# SINTETIZADOR_Y_DDS_SLAVE.net
KiCad netlist of a schematic drawn in Altium Designer
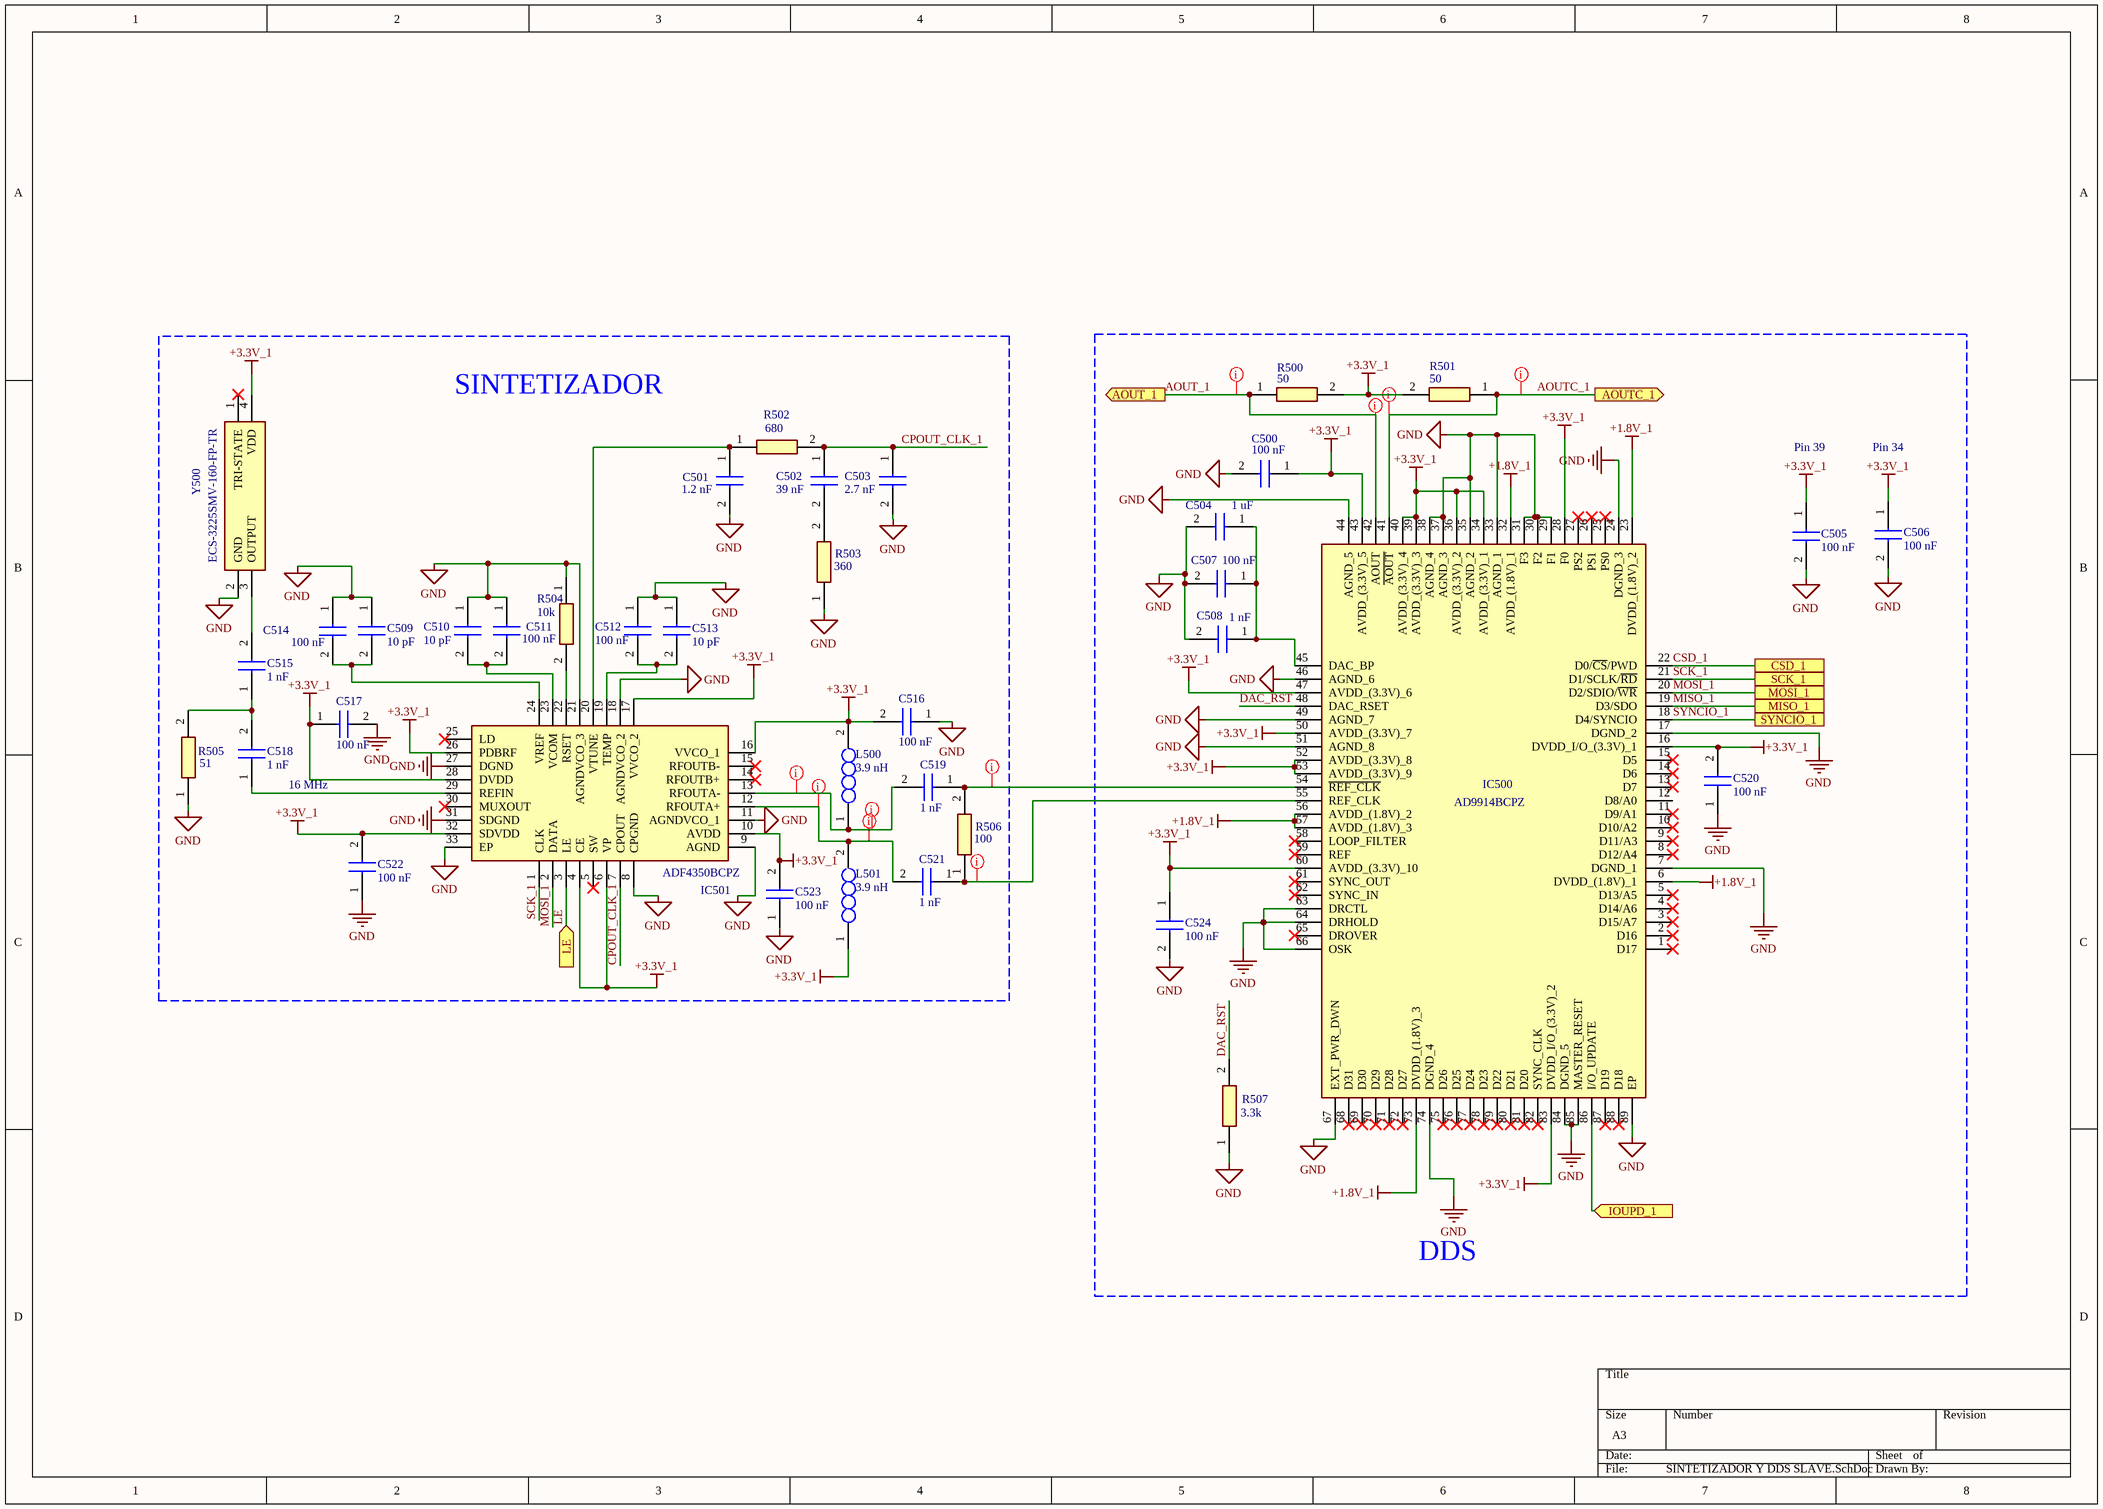
[diagram p0: SINTETIZADOR Y DDS SLAVE.SchDoc]

(export (version "E")
  (design (tool "Eeschema 10.0.6"))
  (components
    (comp (ref "C500")
      (value "100 nF")
      (footprint "SamacSys:C0603")
      (description "Capacitor")
      (fields (field (name "MANUFACTURER_PART_NUMBER") "C0603H470J5GACTU"))
      (libsource (lib "LIBRERIA_GEN_V2.0") (part "C0603H470J5GACTU"))
    )
    (comp (ref "C501")
      (value "1.2 nF")
      (footprint "SamacSys:C0603")
      (description "Capacitor")
      (fields (field (name "MANUFACTURER_PART_NUMBER") "C0603H470J5GACTU"))
      (libsource (lib "LIBRERIA_GEN_V2.0") (part "C0603H470J5GACTU"))
    )
    (comp (ref "C502")
      (value "39 nF")
      (footprint "SamacSys:C0603")
      (description "Capacitor")
      (fields (field (name "MANUFACTURER_PART_NUMBER") "C0603H470J5GACTU"))
      (libsource (lib "LIBRERIA_GEN_V2.0") (part "C0603H470J5GACTU"))
    )
    (comp (ref "C503")
      (value "2.7 nF")
      (footprint "SamacSys:C0603")
      (description "Capacitor")
      (fields (field (name "MANUFACTURER_PART_NUMBER") "C0603H470J5GACTU"))
      (libsource (lib "LIBRERIA_GEN_V2.0") (part "C0603H470J5GACTU"))
    )
    (comp (ref "C504")
      (value "1 uF")
      (footprint "SamacSys:C0603")
      (description "Capacitor")
      (fields (field (name "MANUFACTURER_PART_NUMBER") "C0603H470J5GACTU"))
      (libsource (lib "LIBRERIA_GEN_V2.0") (part "C0603H470J5GACTU"))
    )
    (comp (ref "C505")
      (value "100 nF")
      (footprint "SamacSys:C0603")
      (description "Capacitor")
      (fields (field (name "MANUFACTURER_PART_NUMBER") "C0603H470J5GACTU"))
      (libsource (lib "LIBRERIA_GEN_V2.0") (part "C0603H470J5GACTU"))
    )
    (comp (ref "C506")
      (value "100 nF")
      (footprint "SamacSys:C0603")
      (description "Capacitor")
      (fields (field (name "MANUFACTURER_PART_NUMBER") "C0603H470J5GACTU"))
      (libsource (lib "LIBRERIA_GEN_V2.0") (part "C0603H470J5GACTU"))
    )
    (comp (ref "C507")
      (value "100 nF")
      (footprint "SamacSys:C0603")
      (description "Capacitor")
      (fields (field (name "MANUFACTURER_PART_NUMBER") "C0603H470J5GACTU"))
      (libsource (lib "LIBRERIA_GEN_V2.0") (part "C0603H470J5GACTU"))
    )
    (comp (ref "C508")
      (value "1 nF")
      (footprint "SamacSys:C0603")
      (description "Capacitor")
      (fields (field (name "MANUFACTURER_PART_NUMBER") "C0603H470J5GACTU"))
      (libsource (lib "LIBRERIA_GEN_V2.0") (part "C0603H470J5GACTU"))
    )
    (comp (ref "C509")
      (value "10 pF")
      (footprint "SamacSys:C0603")
      (description "Capacitor")
      (fields (field (name "MANUFACTURER_PART_NUMBER") "C0603H470J5GACTU"))
      (libsource (lib "LIBRERIA_GEN_V2.0") (part "C0603H470J5GACTU"))
    )
    (comp (ref "C510")
      (value "10 pF")
      (footprint "SamacSys:C0603")
      (description "Capacitor")
      (fields (field (name "MANUFACTURER_PART_NUMBER") "C0603H470J5GACTU"))
      (libsource (lib "LIBRERIA_GEN_V2.0") (part "C0603H470J5GACTU"))
    )
    (comp (ref "C511")
      (value "100 nF")
      (footprint "SamacSys:C0603")
      (description "Capacitor")
      (fields (field (name "MANUFACTURER_PART_NUMBER") "C0603H470J5GACTU"))
      (libsource (lib "LIBRERIA_GEN_V2.0") (part "C0603H470J5GACTU"))
    )
    (comp (ref "C512")
      (value "100 nF")
      (footprint "SamacSys:C0603")
      (description "Capacitor")
      (fields (field (name "MANUFACTURER_PART_NUMBER") "C0603H470J5GACTU"))
      (libsource (lib "LIBRERIA_GEN_V2.0") (part "C0603H470J5GACTU"))
    )
    (comp (ref "C513")
      (value "10 pF")
      (footprint "SamacSys:C0603")
      (description "Capacitor")
      (fields (field (name "MANUFACTURER_PART_NUMBER") "C0603H470J5GACTU"))
      (libsource (lib "LIBRERIA_GEN_V2.0") (part "C0603H470J5GACTU"))
    )
    (comp (ref "C514")
      (value "100 nF")
      (footprint "SamacSys:C0603")
      (description "Capacitor")
      (fields (field (name "MANUFACTURER_PART_NUMBER") "C0603H470J5GACTU"))
      (libsource (lib "LIBRERIA_GEN_V2.0") (part "C0603H470J5GACTU"))
    )
    (comp (ref "C515")
      (value "1 nF")
      (footprint "SamacSys:C0603")
      (description "Capacitor")
      (fields (field (name "MANUFACTURER_PART_NUMBER") "C0603H470J5GACTU"))
      (libsource (lib "LIBRERIA_GEN_V2.0") (part "C0603H470J5GACTU"))
    )
    (comp (ref "C516")
      (value "100 nF")
      (footprint "SamacSys:C0603")
      (description "Capacitor")
      (fields (field (name "MANUFACTURER_PART_NUMBER") "C0603H470J5GACTU"))
      (libsource (lib "LIBRERIA_GEN_V2.0") (part "C0603H470J5GACTU"))
    )
    (comp (ref "C517")
      (value "100 nF")
      (footprint "SamacSys:C0603")
      (description "Capacitor")
      (fields (field (name "MANUFACTURER_PART_NUMBER") "C0603H470J5GACTU"))
      (libsource (lib "LIBRERIA_GEN_V2.0") (part "C0603H470J5GACTU"))
    )
    (comp (ref "C518")
      (value "1 nF")
      (footprint "SamacSys:C0603")
      (description "Capacitor")
      (fields (field (name "MANUFACTURER_PART_NUMBER") "C0603H470J5GACTU"))
      (libsource (lib "LIBRERIA_GEN_V2.0") (part "C0603H470J5GACTU"))
    )
    (comp (ref "C519")
      (value "1 nF")
      (footprint "SamacSys:C0603")
      (description "Capacitor")
      (fields (field (name "MANUFACTURER_PART_NUMBER") "C0603H470J5GACTU"))
      (libsource (lib "LIBRERIA_GEN_V2.0") (part "C0603H470J5GACTU"))
    )
    (comp (ref "C520")
      (value "100 nF")
      (footprint "SamacSys:C0603")
      (description "Capacitor")
      (fields (field (name "MANUFACTURER_PART_NUMBER") "C0603H470J5GACTU"))
      (libsource (lib "LIBRERIA_GEN_V2.0") (part "C0603H470J5GACTU"))
    )
    (comp (ref "C521")
      (value "1 nF")
      (footprint "SamacSys:C0603")
      (description "Capacitor")
      (fields (field (name "MANUFACTURER_PART_NUMBER") "C0603H470J5GACTU"))
      (libsource (lib "LIBRERIA_GEN_V2.0") (part "C0603H470J5GACTU"))
    )
    (comp (ref "C522")
      (value "100 nF")
      (footprint "SamacSys:C0603")
      (description "Capacitor")
      (fields (field (name "MANUFACTURER_PART_NUMBER") "C0603H470J5GACTU"))
      (libsource (lib "LIBRERIA_GEN_V2.0") (part "C0603H470J5GACTU"))
    )
    (comp (ref "C523")
      (value "100 nF")
      (footprint "SamacSys:C0603")
      (description "Capacitor")
      (fields (field (name "MANUFACTURER_PART_NUMBER") "C0603H470J5GACTU"))
      (libsource (lib "LIBRERIA_GEN_V2.0") (part "C0603H470J5GACTU"))
    )
    (comp (ref "C524")
      (value "100 nF")
      (footprint "SamacSys:C0603")
      (description "Capacitor")
      (fields (field (name "MANUFACTURER_PART_NUMBER") "C0603H470J5GACTU"))
      (libsource (lib "LIBRERIA_GEN_V2.0") (part "C0603H470J5GACTU"))
    )
    (comp (ref "IC500")
      (value "AD9914BCPZ")
      (footprint "SamacSys:QFN50P1200X1200X90-89N-D")
      (description "Integrated Circuit")
      (fields (field (name "MOUSER PART NUMBER") "584-AD9914BCPZ"))
      (libsource (lib "LIBRERIA_GEN_V2.0") (part "AD9914BCPZ"))
    )
    (comp (ref "IC501")
      (value "ADF4350BCPZ")
      (footprint "SamacSys:QFN50P500X500X100-33N")
      (description "Integrated Circuit")
      (fields (field (name "MOUSER PART NUMBER") "584-ADF4350BCPZ"))
      (libsource (lib "LIBRERIA_GEN_V2.0") (part "ADF4350BCPZ"))
    )
    (comp (ref "L500")
      (value "3.9 nH")
      (footprint "SamacSys:INDC1608X95N")
      (description "Inductor")
      (fields
        (field (name "MANUFACTURER_PART_NUMBER") "AIML-0603-100K-T")
        (field (name "MOUSER PART NUMBER") "815-AIML-0603-100KT")
      )
      (libsource (lib "*") (part "AIML-0603-100K-T"))
    )
    (comp (ref "L501")
      (value "3.9 nH")
      (footprint "SamacSys:INDC1608X95N")
      (description "Inductor")
      (fields
        (field (name "MANUFACTURER_PART_NUMBER") "AIML-0603-100K-T")
        (field (name "MOUSER PART NUMBER") "815-AIML-0603-100KT")
      )
      (libsource (lib "*") (part "AIML-0603-100K-T"))
    )
    (comp (ref "R500")
      (value "50")
      (footprint "SamacSys:RESC1608X55N")
      (description "Resistor")
      (fields
        (field (name "MANUFACTURER_PART_NUMBER") "CR0603-FX-1431ELF")
        (field (name "MOUSER PART NUMBER") "652-CR0603FX-1431ELF")
      )
      (libsource (lib "LIBRERIA_GEN_V2.0") (part "CR0603-FX-1431ELF"))
    )
    (comp (ref "R501")
      (value "50")
      (footprint "SamacSys:RESC1608X55N")
      (description "Resistor")
      (fields
        (field (name "MANUFACTURER_PART_NUMBER") "CR0603-FX-1431ELF")
        (field (name "MOUSER PART NUMBER") "652-CR0603FX-1431ELF")
      )
      (libsource (lib "") (part "CR0603-FX-1431ELF_1"))
    )
    (comp (ref "R502")
      (value "680")
      (footprint "SamacSys:RESC1608X55N")
      (description "Resistor")
      (fields
        (field (name "MANUFACTURER_PART_NUMBER") "CR0603-FX-1431ELF")
        (field (name "MOUSER PART NUMBER") "652-CR0603FX-1431ELF")
      )
      (libsource (lib "LIBRERIA_GEN_V2.0") (part "CR0603-FX-1431ELF"))
    )
    (comp (ref "R503")
      (value "360")
      (footprint "SamacSys:RESC1608X55N")
      (description "Resistor")
      (fields
        (field (name "MANUFACTURER_PART_NUMBER") "CR0603-FX-1431ELF")
        (field (name "MOUSER PART NUMBER") "652-CR0603FX-1431ELF")
      )
      (libsource (lib "") (part "CR0603-FX-1431ELF_3"))
    )
    (comp (ref "R504")
      (value "10k")
      (footprint "SamacSys:RESC1608X55N")
      (description "Resistor")
      (fields
        (field (name "MANUFACTURER_PART_NUMBER") "CR0603-FX-1431ELF")
        (field (name "MOUSER PART NUMBER") "652-CR0603FX-1431ELF")
      )
      (libsource (lib "") (part "CR0603-FX-1431ELF_2"))
    )
    (comp (ref "R505")
      (value "51")
      (footprint "SamacSys:RESC1608X55N")
      (description "Resistor")
      (fields
        (field (name "MANUFACTURER_PART_NUMBER") "CR0603-FX-1431ELF")
        (field (name "MOUSER PART NUMBER") "652-CR0603FX-1431ELF")
      )
      (libsource (lib "") (part "CR0603-FX-1431ELF_3"))
    )
    (comp (ref "R506")
      (value "100")
      (footprint "SamacSys:RESC1608X55N")
      (description "Resistor")
      (fields
        (field (name "MANUFACTURER_PART_NUMBER") "CR0603-FX-1431ELF")
        (field (name "MOUSER PART NUMBER") "652-CR0603FX-1431ELF")
      )
      (libsource (lib "") (part "CR0603-FX-1431ELF_3"))
    )
    (comp (ref "R507")
      (value "3.3k")
      (footprint "SamacSys:RESC1608X55N")
      (description "Resistor")
      (fields
        (field (name "MANUFACTURER_PART_NUMBER") "CR0603-FX-1431ELF")
        (field (name "MOUSER PART NUMBER") "652-CR0603FX-1431ELF")
      )
      (libsource (lib "") (part "CR0603-FX-1431ELF_3"))
    )
    (comp (ref "Y500")
      (value "ECS-3225SMV-160-FP-TR")
      (footprint "SamacSys:ECS3225SMV160FPTR")
      (description "Crystal or Oscillator")
      (fields (field (name "MOUSER PART NUMBER") "520-3225SMV-160-FPT"))
      (libsource (lib "LIBRERIA_GEN_V2.0") (part "ECS-3225SMV-160-FP-TR"))
    )
  )
  (nets
    (net (code "1") (name "+1.8V_1") (class "Default")
      (node (ref "IC500") (pin "23") (pinfunction "DVDD_(1.8V)_2_23") (pintype "passive"))
      (node (ref "IC500") (pin "32") (pinfunction "AVDD_(1.8V)_1_32") (pintype "passive"))
      (node (ref "IC500") (pin "56") (pinfunction "AVDD_(1.8V)_2_56") (pintype "passive"))
      (node (ref "IC500") (pin "57") (pinfunction "AVDD_(1.8V)_3_57") (pintype "passive"))
      (node (ref "IC500") (pin "6") (pinfunction "DVDD_(1.8V)_1_6") (pintype "passive"))
      (node (ref "IC500") (pin "73") (pinfunction "DVDD_(1.8V)_3_73") (pintype "passive"))
    )
    (net (code "2") (name "+3.3V_1") (class "Default")
      (node (ref "C500") (pin "1") (pinfunction "1_1") (pintype "passive"))
      (node (ref "C505") (pin "1") (pinfunction "1_1") (pintype "passive"))
      (node (ref "C506") (pin "1") (pinfunction "1_1") (pintype "passive"))
      (node (ref "C516") (pin "2") (pinfunction "2_2") (pintype "passive"))
      (node (ref "C517") (pin "1") (pinfunction "1_1") (pintype "passive"))
      (node (ref "C520") (pin "2") (pinfunction "2_2") (pintype "passive"))
      (node (ref "C522") (pin "2") (pinfunction "2_2") (pintype "passive"))
      (node (ref "C523") (pin "2") (pinfunction "2_2") (pintype "passive"))
      (node (ref "C524") (pin "1") (pinfunction "1_1") (pintype "passive"))
      (node (ref "IC500") (pin "16") (pinfunction "DVDD_I/O_(3.3V)_1_16") (pintype "passive"))
      (node (ref "IC500") (pin "28") (pinfunction "F0_28") (pintype "passive"))
      (node (ref "IC500") (pin "34") (pinfunction "AVDD_(3.3V)_1_34") (pintype "passive"))
      (node (ref "IC500") (pin "36") (pinfunction "AVDD_(3.3V)_2_36") (pintype "passive"))
      (node (ref "IC500") (pin "39") (pinfunction "AVDD_(3.3V)_3_39") (pintype "passive"))
      (node (ref "IC500") (pin "40") (pinfunction "AVDD_(3.3V)_4_40") (pintype "passive"))
      (node (ref "IC500") (pin "43") (pinfunction "AVDD_(3.3V)_5_43") (pintype "passive"))
      (node (ref "IC500") (pin "47") (pinfunction "AVDD_(3.3V)_6_47") (pintype "passive"))
      (node (ref "IC500") (pin "50") (pinfunction "AVDD_(3.3V)_7_50") (pintype "passive"))
      (node (ref "IC500") (pin "52") (pinfunction "AVDD_(3.3V)_8_52") (pintype "passive"))
      (node (ref "IC500") (pin "53") (pinfunction "AVDD_(3.3V)_9_53") (pintype "passive"))
      (node (ref "IC500") (pin "60") (pinfunction "AVDD_(3.3V)_10_60") (pintype "passive"))
      (node (ref "IC500") (pin "83") (pinfunction "DVDD_I/O_(3.3V)_2_83") (pintype "passive"))
      (node (ref "IC501") (pin "10") (pinfunction "AVDD_10") (pintype "passive"))
      (node (ref "IC501") (pin "16") (pinfunction "VVCO_1_16") (pintype "passive"))
      (node (ref "IC501") (pin "17") (pinfunction "VVCO_2_17") (pintype "passive"))
      (node (ref "IC501") (pin "26") (pinfunction "PDBRF_26") (pintype "passive"))
      (node (ref "IC501") (pin "28") (pinfunction "DVDD_28") (pintype "passive"))
      (node (ref "IC501") (pin "32") (pinfunction "SDVDD_32") (pintype "passive"))
      (node (ref "IC501") (pin "4") (pinfunction "CE_4") (pintype "passive"))
      (node (ref "IC501") (pin "6") (pinfunction "VP_6") (pintype "passive"))
      (node (ref "L500") (pin "2") (pinfunction "2_2") (pintype "passive"))
      (node (ref "L501") (pin "1") (pinfunction "1_1") (pintype "passive"))
      (node (ref "R500") (pin "2") (pinfunction "2_2") (pintype "passive"))
      (node (ref "R501") (pin "2") (pinfunction "2_2") (pintype "passive"))
      (node (ref "Y500") (pin "4") (pinfunction "VDD_4") (pintype "passive"))
    )
    (net (code "3") (name "/AOUTC_1") (class "Default")
      (node (ref "IC500") (pin "41") (pinfunction "~{AOUT}_41") (pintype "passive"))
      (node (ref "R501") (pin "1") (pinfunction "1_1") (pintype "passive"))
    )
    (net (code "4") (name "/AOUT_1") (class "Default")
      (node (ref "IC500") (pin "42") (pinfunction "AOUT_42") (pintype "passive"))
      (node (ref "R500") (pin "1") (pinfunction "1_1") (pintype "passive"))
    )
    (net (code "5") (name "/CPOUT_CLK_1") (class "Default")
      (node (ref "C502") (pin "1") (pinfunction "1_1") (pintype "passive"))
      (node (ref "C503") (pin "1") (pinfunction "1_1") (pintype "passive"))
      (node (ref "IC501") (pin "7") (pinfunction "CPOUT_7") (pintype "passive"))
      (node (ref "R502") (pin "2") (pinfunction "2_2") (pintype "passive"))
    )
    (net (code "6") (name "/CSD_1") (class "Default")
      (node (ref "IC500") (pin "22") (pinfunction "D0/~{CS}/PWD_22") (pintype "passive"))
    )
    (net (code "7") (name "/DAC_RST") (class "Default")
      (node (ref "IC500") (pin "48") (pinfunction "DAC_RSET_48") (pintype "passive"))
      (node (ref "R507") (pin "2") (pinfunction "2_2") (pintype "passive"))
    )
    (net (code "8") (name "/IOUPD_1") (class "Default")
      (node (ref "IC500") (pin "86") (pinfunction "I/O_UPDATE_86") (pintype "passive"))
    )
    (net (code "9") (name "/LE") (class "Default")
      (node (ref "IC501") (pin "3") (pinfunction "LE_3") (pintype "passive"))
    )
    (net (code "10") (name "/MISO_1") (class "Default")
      (node (ref "IC500") (pin "19") (pinfunction "D3/SDO_19") (pintype "passive"))
    )
    (net (code "11") (name "/MOSI_1") (class "Default")
      (node (ref "IC500") (pin "20") (pinfunction "D2/SDIO/~{WR}_20") (pintype "passive"))
      (node (ref "IC501") (pin "2") (pinfunction "DATA_2") (pintype "passive"))
    )
    (net (code "12") (name "/SCK_1") (class "Default")
      (node (ref "IC500") (pin "21") (pinfunction "D1/SCLK/~{RD}_21") (pintype "passive"))
      (node (ref "IC501") (pin "1") (pinfunction "CLK_1") (pintype "passive"))
    )
    (net (code "13") (name "/SYNCIO_1") (class "Default")
      (node (ref "IC500") (pin "18") (pinfunction "D4/SYNCIO_18") (pintype "passive"))
    )
    (net (code "14") (name "GND") (class "Default")
      (node (ref "C500") (pin "2") (pinfunction "2_2") (pintype "passive"))
      (node (ref "C501") (pin "2") (pinfunction "2_2") (pintype "passive"))
      (node (ref "C503") (pin "2") (pinfunction "2_2") (pintype "passive"))
      (node (ref "C504") (pin "2") (pinfunction "2_2") (pintype "passive"))
      (node (ref "C505") (pin "2") (pinfunction "2_2") (pintype "passive"))
      (node (ref "C506") (pin "2") (pinfunction "2_2") (pintype "passive"))
      (node (ref "C507") (pin "2") (pinfunction "2_2") (pintype "passive"))
      (node (ref "C508") (pin "2") (pinfunction "2_2") (pintype "passive"))
      (node (ref "C509") (pin "1") (pinfunction "1_1") (pintype "passive"))
      (node (ref "C510") (pin "1") (pinfunction "1_1") (pintype "passive"))
      (node (ref "C511") (pin "1") (pinfunction "1_1") (pintype "passive"))
      (node (ref "C512") (pin "1") (pinfunction "1_1") (pintype "passive"))
      (node (ref "C513") (pin "1") (pinfunction "1_1") (pintype "passive"))
      (node (ref "C514") (pin "1") (pinfunction "1_1") (pintype "passive"))
      (node (ref "C516") (pin "1") (pinfunction "1_1") (pintype "passive"))
      (node (ref "C517") (pin "2") (pinfunction "2_2") (pintype "passive"))
      (node (ref "C520") (pin "1") (pinfunction "1_1") (pintype "passive"))
      (node (ref "C522") (pin "1") (pinfunction "1_1") (pintype "passive"))
      (node (ref "C523") (pin "1") (pinfunction "1_1") (pintype "passive"))
      (node (ref "C524") (pin "2") (pinfunction "2_2") (pintype "passive"))
      (node (ref "IC500") (pin "17") (pinfunction "DGND_2_17") (pintype "passive"))
      (node (ref "IC500") (pin "24") (pinfunction "DGND_3_24") (pintype "passive"))
      (node (ref "IC500") (pin "29") (pinfunction "F1_29") (pintype "passive"))
      (node (ref "IC500") (pin "30") (pinfunction "F2_30") (pintype "passive"))
      (node (ref "IC500") (pin "31") (pinfunction "F3_31") (pintype "passive"))
      (node (ref "IC500") (pin "33") (pinfunction "AGND_1_33") (pintype "passive"))
      (node (ref "IC500") (pin "35") (pinfunction "AGND_2_35") (pintype "passive"))
      (node (ref "IC500") (pin "37") (pinfunction "AGND_3_37") (pintype "passive"))
      (node (ref "IC500") (pin "38") (pinfunction "AGND_4_38") (pintype "passive"))
      (node (ref "IC500") (pin "44") (pinfunction "AGND_5_44") (pintype "passive"))
      (node (ref "IC500") (pin "46") (pinfunction "AGND_6_46") (pintype "passive"))
      (node (ref "IC500") (pin "49") (pinfunction "AGND_7_49") (pintype "passive"))
      (node (ref "IC500") (pin "51") (pinfunction "AGND_8_51") (pintype "passive"))
      (node (ref "IC500") (pin "63") (pinfunction "DRCTL_63") (pintype "passive"))
      (node (ref "IC500") (pin "64") (pinfunction "DRHOLD_64") (pintype "passive"))
      (node (ref "IC500") (pin "66") (pinfunction "OSK_66") (pintype "passive"))
      (node (ref "IC500") (pin "67") (pinfunction "EXT_PWR_DWN_67") (pintype "passive"))
      (node (ref "IC500") (pin "7") (pinfunction "DGND_1_7") (pintype "passive"))
      (node (ref "IC500") (pin "74") (pinfunction "DGND_4_74") (pintype "passive"))
      (node (ref "IC500") (pin "84") (pinfunction "DGND_5_84") (pintype "passive"))
      (node (ref "IC500") (pin "85") (pinfunction "MASTER_RESET_85") (pintype "passive"))
      (node (ref "IC500") (pin "89") (pinfunction "EP_89") (pintype "passive"))
      (node (ref "IC501") (pin "11") (pinfunction "AGNDVCO_1_11") (pintype "passive"))
      (node (ref "IC501") (pin "18") (pinfunction "AGNDVCO_2_18") (pintype "passive"))
      (node (ref "IC501") (pin "21") (pinfunction "AGNDVCO_3_21") (pintype "passive"))
      (node (ref "IC501") (pin "27") (pinfunction "DGND_27") (pintype "passive"))
      (node (ref "IC501") (pin "31") (pinfunction "SDGND_31") (pintype "passive"))
      (node (ref "IC501") (pin "33") (pinfunction "EP_33") (pintype "passive"))
      (node (ref "IC501") (pin "8") (pinfunction "CPGND_8") (pintype "passive"))
      (node (ref "IC501") (pin "9") (pinfunction "AGND_9") (pintype "passive"))
      (node (ref "R503") (pin "1") (pinfunction "1_1") (pintype "passive"))
      (node (ref "R504") (pin "1") (pinfunction "1_1") (pintype "passive"))
      (node (ref "R505") (pin "1") (pinfunction "1_1") (pintype "passive"))
      (node (ref "R507") (pin "1") (pinfunction "1_1") (pintype "passive"))
      (node (ref "Y500") (pin "2") (pinfunction "GND_2") (pintype "passive"))
    )
    (net (code "15") (name "Net-(C502-Pad2)") (class "Default")
      (node (ref "C502") (pin "2") (pinfunction "2_2") (pintype "passive"))
      (node (ref "R503") (pin "2") (pinfunction "2_2") (pintype "passive"))
    )
    (net (code "16") (name "Net-(C515-Pad1)") (class "Default")
      (node (ref "C515") (pin "1") (pinfunction "1_1") (pintype "passive"))
      (node (ref "C518") (pin "2") (pinfunction "2_2") (pintype "passive"))
      (node (ref "R505") (pin "2") (pinfunction "2_2") (pintype "passive"))
    )
    (net (code "17") (name "Net-(IC500-DAC_BP)") (class "Default")
      (node (ref "C504") (pin "1") (pinfunction "1_1") (pintype "passive"))
      (node (ref "C507") (pin "1") (pinfunction "1_1") (pintype "passive"))
      (node (ref "C508") (pin "1") (pinfunction "1_1") (pintype "passive"))
      (node (ref "IC500") (pin "45") (pinfunction "DAC_BP_45") (pintype "passive"))
    )
    (net (code "18") (name "Net-(IC500-REF_CLK)") (class "Default")
      (node (ref "C521") (pin "1") (pinfunction "1_1") (pintype "passive"))
      (node (ref "IC500") (pin "55") (pinfunction "REF_CLK_55") (pintype "passive"))
      (node (ref "R506") (pin "1") (pinfunction "1_1") (pintype "passive"))
    )
    (net (code "19") (name "Net-(IC500-~{REF_CLK})") (class "Default")
      (node (ref "C519") (pin "1") (pinfunction "1_1") (pintype "passive"))
      (node (ref "IC500") (pin "54") (pinfunction "~{REF_CLK}_54") (pintype "passive"))
      (node (ref "R506") (pin "2") (pinfunction "2_2") (pintype "passive"))
    )
    (net (code "20") (name "Net-(IC501-REFIN)") (class "Default")
      (node (ref "C518") (pin "1") (pinfunction "1_1") (pintype "passive"))
      (node (ref "IC501") (pin "29") (pinfunction "REFIN_29") (pintype "passive"))
    )
    (net (code "21") (name "Net-(IC501-RFOUTA+)") (class "Default")
      (node (ref "C521") (pin "2") (pinfunction "2_2") (pintype "passive"))
      (node (ref "IC501") (pin "12") (pinfunction "RFOUTA+_12") (pintype "passive"))
      (node (ref "L501") (pin "2") (pinfunction "2_2") (pintype "passive"))
    )
    (net (code "22") (name "Net-(IC501-RFOUTA-)") (class "Default")
      (node (ref "C519") (pin "2") (pinfunction "2_2") (pintype "passive"))
      (node (ref "IC501") (pin "13") (pinfunction "RFOUTA-_13") (pintype "passive"))
      (node (ref "L500") (pin "1") (pinfunction "1_1") (pintype "passive"))
    )
    (net (code "23") (name "Net-(IC501-RSET)") (class "Default")
      (node (ref "IC501") (pin "22") (pinfunction "RSET_22") (pintype "passive"))
      (node (ref "R504") (pin "2") (pinfunction "2_2") (pintype "passive"))
    )
    (net (code "24") (name "Net-(IC501-TEMP)") (class "Default")
      (node (ref "C512") (pin "2") (pinfunction "2_2") (pintype "passive"))
      (node (ref "C513") (pin "2") (pinfunction "2_2") (pintype "passive"))
      (node (ref "IC501") (pin "19") (pinfunction "TEMP_19") (pintype "passive"))
    )
    (net (code "25") (name "Net-(IC501-VCOM)") (class "Default")
      (node (ref "C510") (pin "2") (pinfunction "2_2") (pintype "passive"))
      (node (ref "C511") (pin "2") (pinfunction "2_2") (pintype "passive"))
      (node (ref "IC501") (pin "23") (pinfunction "VCOM_23") (pintype "passive"))
    )
    (net (code "26") (name "Net-(IC501-VREF)") (class "Default")
      (node (ref "C509") (pin "2") (pinfunction "2_2") (pintype "passive"))
      (node (ref "C514") (pin "2") (pinfunction "2_2") (pintype "passive"))
      (node (ref "IC501") (pin "24") (pinfunction "VREF_24") (pintype "passive"))
    )
    (net (code "27") (name "Net-(IC501-VTUNE)") (class "Default")
      (node (ref "C501") (pin "1") (pinfunction "1_1") (pintype "passive"))
      (node (ref "IC501") (pin "20") (pinfunction "VTUNE_20") (pintype "passive"))
      (node (ref "R502") (pin "1") (pinfunction "1_1") (pintype "passive"))
    )
    (net (code "28") (name "Net-(Y500-OUTPUT)") (class "Default")
      (node (ref "C515") (pin "2") (pinfunction "2_2") (pintype "passive"))
      (node (ref "Y500") (pin "3") (pinfunction "OUTPUT_3") (pintype "passive"))
    )
    (net (code "29") (name "unconnected-(IC500-D5-Pad15)") (class "Default")
      (node (ref "IC500") (pin "15") (pinfunction "D5_15") (pintype "passive+no_connect"))
    )
    (net (code "30") (name "unconnected-(IC500-D6-Pad14)") (class "Default")
      (node (ref "IC500") (pin "14") (pinfunction "D6_14") (pintype "passive+no_connect"))
    )
    (net (code "31") (name "unconnected-(IC500-D7-Pad13)") (class "Default")
      (node (ref "IC500") (pin "13") (pinfunction "D7_13") (pintype "passive+no_connect"))
    )
    (net (code "32") (name "unconnected-(IC500-D8{slash}A0-Pad12)") (class "Default")
      (node (ref "IC500") (pin "12") (pinfunction "D8/A0_12") (pintype "passive"))
    )
    (net (code "33") (name "unconnected-(IC500-D9{slash}A1-Pad11)") (class "Default")
      (node (ref "IC500") (pin "11") (pinfunction "D9/A1_11") (pintype "passive+no_connect"))
    )
    (net (code "34") (name "unconnected-(IC500-D10{slash}A2-Pad10)") (class "Default")
      (node (ref "IC500") (pin "10") (pinfunction "D10/A2_10") (pintype "passive+no_connect"))
    )
    (net (code "35") (name "unconnected-(IC500-D11{slash}A3-Pad9)") (class "Default")
      (node (ref "IC500") (pin "9") (pinfunction "D11/A3_9") (pintype "passive+no_connect"))
    )
    (net (code "36") (name "unconnected-(IC500-D12{slash}A4-Pad8)") (class "Default")
      (node (ref "IC500") (pin "8") (pinfunction "D12/A4_8") (pintype "passive+no_connect"))
    )
    (net (code "37") (name "unconnected-(IC500-D13{slash}A5-Pad5)") (class "Default")
      (node (ref "IC500") (pin "5") (pinfunction "D13/A5_5") (pintype "passive+no_connect"))
    )
    (net (code "38") (name "unconnected-(IC500-D14{slash}A6-Pad4)") (class "Default")
      (node (ref "IC500") (pin "4") (pinfunction "D14/A6_4") (pintype "passive+no_connect"))
    )
    (net (code "39") (name "unconnected-(IC500-D15{slash}A7-Pad3)") (class "Default")
      (node (ref "IC500") (pin "3") (pinfunction "D15/A7_3") (pintype "passive+no_connect"))
    )
    (net (code "40") (name "unconnected-(IC500-D16-Pad2)") (class "Default")
      (node (ref "IC500") (pin "2") (pinfunction "D16_2") (pintype "passive+no_connect"))
    )
    (net (code "41") (name "unconnected-(IC500-D17-Pad1)") (class "Default")
      (node (ref "IC500") (pin "1") (pinfunction "D17_1") (pintype "passive+no_connect"))
    )
    (net (code "42") (name "unconnected-(IC500-D18-Pad88)") (class "Default")
      (node (ref "IC500") (pin "88") (pinfunction "D18_88") (pintype "passive+no_connect"))
    )
    (net (code "43") (name "unconnected-(IC500-D19-Pad87)") (class "Default")
      (node (ref "IC500") (pin "87") (pinfunction "D19_87") (pintype "passive+no_connect"))
    )
    (net (code "44") (name "unconnected-(IC500-D20-Pad81)") (class "Default")
      (node (ref "IC500") (pin "81") (pinfunction "D20_81") (pintype "passive+no_connect"))
    )
    (net (code "45") (name "unconnected-(IC500-D21-Pad80)") (class "Default")
      (node (ref "IC500") (pin "80") (pinfunction "D21_80") (pintype "passive+no_connect"))
    )
    (net (code "46") (name "unconnected-(IC500-D22-Pad79)") (class "Default")
      (node (ref "IC500") (pin "79") (pinfunction "D22_79") (pintype "passive+no_connect"))
    )
    (net (code "47") (name "unconnected-(IC500-D23-Pad78)") (class "Default")
      (node (ref "IC500") (pin "78") (pinfunction "D23_78") (pintype "passive+no_connect"))
    )
    (net (code "48") (name "unconnected-(IC500-D24-Pad77)") (class "Default")
      (node (ref "IC500") (pin "77") (pinfunction "D24_77") (pintype "passive+no_connect"))
    )
    (net (code "49") (name "unconnected-(IC500-D25-Pad76)") (class "Default")
      (node (ref "IC500") (pin "76") (pinfunction "D25_76") (pintype "passive+no_connect"))
    )
    (net (code "50") (name "unconnected-(IC500-D26-Pad75)") (class "Default")
      (node (ref "IC500") (pin "75") (pinfunction "D26_75") (pintype "passive+no_connect"))
    )
    (net (code "51") (name "unconnected-(IC500-D27-Pad72)") (class "Default")
      (node (ref "IC500") (pin "72") (pinfunction "D27_72") (pintype "passive+no_connect"))
    )
    (net (code "52") (name "unconnected-(IC500-D28-Pad71)") (class "Default")
      (node (ref "IC500") (pin "71") (pinfunction "D28_71") (pintype "passive+no_connect"))
    )
    (net (code "53") (name "unconnected-(IC500-D29-Pad70)") (class "Default")
      (node (ref "IC500") (pin "70") (pinfunction "D29_70") (pintype "passive+no_connect"))
    )
    (net (code "54") (name "unconnected-(IC500-D30-Pad69)") (class "Default")
      (node (ref "IC500") (pin "69") (pinfunction "D30_69") (pintype "passive+no_connect"))
    )
    (net (code "55") (name "unconnected-(IC500-D31-Pad68)") (class "Default")
      (node (ref "IC500") (pin "68") (pinfunction "D31_68") (pintype "passive+no_connect"))
    )
    (net (code "56") (name "unconnected-(IC500-DROVER-Pad65)") (class "Default")
      (node (ref "IC500") (pin "65") (pinfunction "DROVER_65") (pintype "passive+no_connect"))
    )
    (net (code "57") (name "unconnected-(IC500-LOOP_FILTER-Pad58)") (class "Default")
      (node (ref "IC500") (pin "58") (pinfunction "LOOP_FILTER_58") (pintype "passive+no_connect"))
    )
    (net (code "58") (name "unconnected-(IC500-PS0-Pad25)") (class "Default")
      (node (ref "IC500") (pin "25") (pinfunction "PS0_25") (pintype "passive+no_connect"))
    )
    (net (code "59") (name "unconnected-(IC500-PS1-Pad26)") (class "Default")
      (node (ref "IC500") (pin "26") (pinfunction "PS1_26") (pintype "passive+no_connect"))
    )
    (net (code "60") (name "unconnected-(IC500-PS2-Pad27)") (class "Default")
      (node (ref "IC500") (pin "27") (pinfunction "PS2_27") (pintype "passive+no_connect"))
    )
    (net (code "61") (name "unconnected-(IC500-REF-Pad59)") (class "Default")
      (node (ref "IC500") (pin "59") (pinfunction "REF_59") (pintype "passive+no_connect"))
    )
    (net (code "62") (name "unconnected-(IC500-SYNC_CLK-Pad82)") (class "Default")
      (node (ref "IC500") (pin "82") (pinfunction "SYNC_CLK_82") (pintype "passive+no_connect"))
    )
    (net (code "63") (name "unconnected-(IC500-SYNC_IN-Pad62)") (class "Default")
      (node (ref "IC500") (pin "62") (pinfunction "SYNC_IN_62") (pintype "passive+no_connect"))
    )
    (net (code "64") (name "unconnected-(IC500-SYNC_OUT-Pad61)") (class "Default")
      (node (ref "IC500") (pin "61") (pinfunction "SYNC_OUT_61") (pintype "passive+no_connect"))
    )
    (net (code "65") (name "unconnected-(IC501-LD-Pad25)") (class "Default")
      (node (ref "IC501") (pin "25") (pinfunction "LD_25") (pintype "passive+no_connect"))
    )
    (net (code "66") (name "unconnected-(IC501-MUXOUT-Pad30)") (class "Default")
      (node (ref "IC501") (pin "30") (pinfunction "MUXOUT_30") (pintype "passive+no_connect"))
    )
    (net (code "67") (name "unconnected-(IC501-RFOUTB+-Pad14)") (class "Default")
      (node (ref "IC501") (pin "14") (pinfunction "RFOUTB+_14") (pintype "passive+no_connect"))
    )
    (net (code "68") (name "unconnected-(IC501-RFOUTB--Pad15)") (class "Default")
      (node (ref "IC501") (pin "15") (pinfunction "RFOUTB-_15") (pintype "passive+no_connect"))
    )
    (net (code "69") (name "unconnected-(IC501-SW-Pad5)") (class "Default")
      (node (ref "IC501") (pin "5") (pinfunction "SW_5") (pintype "passive+no_connect"))
    )
    (net (code "70") (name "unconnected-(Y500-TRI-STATE-Pad1)") (class "Default")
      (node (ref "Y500") (pin "1") (pinfunction "TRI-STATE_1") (pintype "passive+no_connect"))
    )
  )
)
